# Timer-Ruler.net
KiCad netlist of a schematic drawn in EAGLE
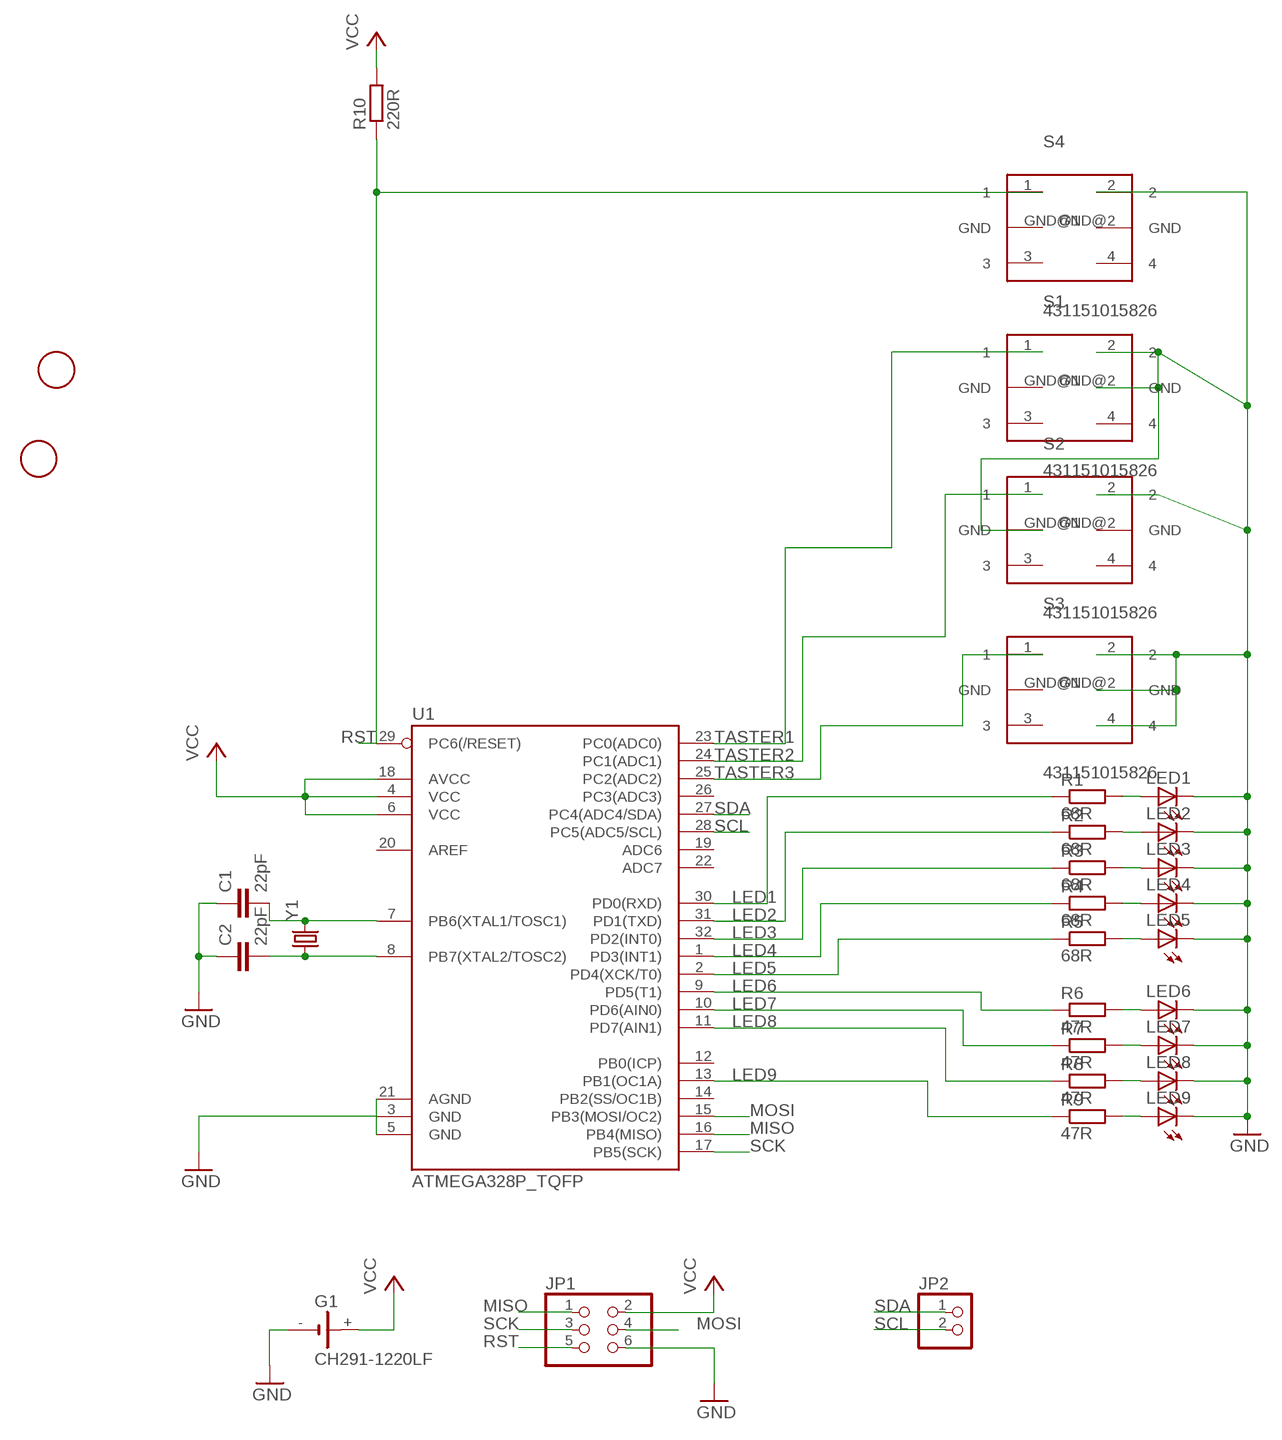
[diagram p0: schematic, sheet 1]

(export (version "E")
  (design (tool "Eeschema 10.0.6"))
  (components
    (comp (ref "C1")
      (value "22pF")
      (footprint "eagle-import:C0603")
      (libsource (lib "eagle-import") (part "C-EUC0603"))
    )
    (comp (ref "C2")
      (value "22pF")
      (footprint "eagle-import:C0603")
      (libsource (lib "eagle-import") (part "C-EUC0603"))
    )
    (comp (ref "G1")
      (value "CH291-1220LF")
      (footprint "eagle-import:CH291-1220LF")
      (libsource (lib "eagle-import") (part "CH291-1220LF"))
    )
    (comp (ref "JP1")
      (value "PINHD-2X3")
      (footprint "eagle-import:2X03")
      (libsource (lib "eagle-import") (part "PINHD-2X3"))
    )
    (comp (ref "JP2")
      (value "PINHD-1X2")
      (footprint "eagle-import:1X02")
      (libsource (lib "eagle-import") (part "PINHD-1X2"))
    )
    (comp (ref "LED1")
      (value "LEDCHIP-LED0805")
      (footprint "eagle-import:CHIP-LED0805")
      (libsource (lib "eagle-import") (part "LEDCHIP-LED0805"))
    )
    (comp (ref "LED2")
      (value "LEDCHIP-LED0805")
      (footprint "eagle-import:CHIP-LED0805")
      (libsource (lib "eagle-import") (part "LEDCHIP-LED0805"))
    )
    (comp (ref "LED3")
      (value "LEDCHIP-LED0805")
      (footprint "eagle-import:CHIP-LED0805")
      (libsource (lib "eagle-import") (part "LEDCHIP-LED0805"))
    )
    (comp (ref "LED4")
      (value "LEDCHIP-LED0805")
      (footprint "eagle-import:CHIP-LED0805")
      (libsource (lib "eagle-import") (part "LEDCHIP-LED0805"))
    )
    (comp (ref "LED5")
      (value "LEDCHIP-LED0805")
      (footprint "eagle-import:CHIP-LED0805")
      (libsource (lib "eagle-import") (part "LEDCHIP-LED0805"))
    )
    (comp (ref "LED6")
      (value "LEDCHIP-LED0805")
      (footprint "eagle-import:CHIP-LED0805")
      (libsource (lib "eagle-import") (part "LEDCHIP-LED0805"))
    )
    (comp (ref "LED7")
      (value "LEDCHIP-LED0805")
      (footprint "eagle-import:CHIP-LED0805")
      (libsource (lib "eagle-import") (part "LEDCHIP-LED0805"))
    )
    (comp (ref "LED8")
      (value "LEDCHIP-LED0805")
      (footprint "eagle-import:CHIP-LED0805")
      (libsource (lib "eagle-import") (part "LEDCHIP-LED0805"))
    )
    (comp (ref "LED9")
      (value "LEDCHIP-LED0805")
      (footprint "eagle-import:CHIP-LED0805")
      (libsource (lib "eagle-import") (part "LEDCHIP-LED0805"))
    )
    (comp (ref "R1")
      (value "68R")
      (footprint "eagle-import:R0603")
      (libsource (lib "eagle-import") (part "R-EU_R0603"))
    )
    (comp (ref "R2")
      (value "68R")
      (footprint "eagle-import:R0603")
      (libsource (lib "eagle-import") (part "R-EU_R0603"))
    )
    (comp (ref "R3")
      (value "68R")
      (footprint "eagle-import:R0603")
      (libsource (lib "eagle-import") (part "R-EU_R0603"))
    )
    (comp (ref "R4")
      (value "68R")
      (footprint "eagle-import:R0603")
      (libsource (lib "eagle-import") (part "R-EU_R0603"))
    )
    (comp (ref "R5")
      (value "68R")
      (footprint "eagle-import:R0603")
      (libsource (lib "eagle-import") (part "R-EU_R0603"))
    )
    (comp (ref "R6")
      (value "47R")
      (footprint "eagle-import:R0603")
      (libsource (lib "eagle-import") (part "R-EU_R0603"))
    )
    (comp (ref "R7")
      (value "47R")
      (footprint "eagle-import:R0603")
      (libsource (lib "eagle-import") (part "R-EU_R0603"))
    )
    (comp (ref "R8")
      (value "47R")
      (footprint "eagle-import:R0603")
      (libsource (lib "eagle-import") (part "R-EU_R0603"))
    )
    (comp (ref "R9")
      (value "47R")
      (footprint "eagle-import:R0603")
      (libsource (lib "eagle-import") (part "R-EU_R0603"))
    )
    (comp (ref "R10")
      (value "220R")
      (footprint "eagle-import:R0603")
      (libsource (lib "eagle-import") (part "R-EU_R0603"))
    )
    (comp (ref "S1")
      (value "431151015826")
      (footprint "eagle-import:431181015816")
      (libsource (lib "eagle-import") (part "431151015826"))
    )
    (comp (ref "S2")
      (value "431151015826")
      (footprint "eagle-import:431181015816")
      (libsource (lib "eagle-import") (part "431151015826"))
    )
    (comp (ref "S3")
      (value "431151015826")
      (footprint "eagle-import:431181015816")
      (libsource (lib "eagle-import") (part "431151015826"))
    )
    (comp (ref "S4")
      (value "431151015826")
      (footprint "eagle-import:431181015816")
      (libsource (lib "eagle-import") (part "431151015826"))
    )
    (comp (ref "U$1")
      (value "FIDUCIAL")
      (footprint "eagle-import:FIDUCIAL_1MM")
      (libsource (lib "eagle-import") (part "FIDUCIAL"))
    )
    (comp (ref "U$2")
      (value "FIDUCIAL")
      (footprint "eagle-import:FIDUCIAL_1MM")
      (libsource (lib "eagle-import") (part "FIDUCIAL"))
    )
    (comp (ref "U1")
      (value "ATMEGA328P_TQFP")
      (footprint "eagle-import:TQFP32-08")
      (libsource (lib "eagle-import") (part "ATMEGA328P_TQFP"))
    )
    (comp (ref "Y1")
      (value "CRYSTALCRYSTAL-SMD-5X3-12.288MHZ")
      (footprint "eagle-import:CRYSTAL-SMD-5X3")
      (libsource (lib "eagle-import") (part "CRYSTALCRYSTAL-SMD-5X3-12.288MHZ"))
    )
  )
  (nets
    (net (code "1") (name "/LED1") (class "Default")
      (node (ref "R1") (pin "1") (pinfunction "1_1") (pintype "passive"))
      (node (ref "U1") (pin "30") (pinfunction "PD0(RXD)_30") (pintype "bidirectional"))
    )
    (net (code "2") (name "/LED2") (class "Default")
      (node (ref "R2") (pin "1") (pinfunction "1_1") (pintype "passive"))
      (node (ref "U1") (pin "31") (pinfunction "PD1(TXD)_31") (pintype "bidirectional"))
    )
    (net (code "3") (name "/LED3") (class "Default")
      (node (ref "R3") (pin "1") (pinfunction "1_1") (pintype "passive"))
      (node (ref "U1") (pin "32") (pinfunction "PD2(INT0)_32") (pintype "bidirectional"))
    )
    (net (code "4") (name "/LED4") (class "Default")
      (node (ref "R4") (pin "1") (pinfunction "1_1") (pintype "passive"))
      (node (ref "U1") (pin "1") (pinfunction "PD3(INT1)_1") (pintype "bidirectional"))
    )
    (net (code "5") (name "/LED5") (class "Default")
      (node (ref "R5") (pin "1") (pinfunction "1_1") (pintype "passive"))
      (node (ref "U1") (pin "2") (pinfunction "PD4(XCK/T0)_2") (pintype "bidirectional"))
    )
    (net (code "6") (name "/LED6") (class "Default")
      (node (ref "R6") (pin "1") (pinfunction "1_1") (pintype "passive"))
      (node (ref "U1") (pin "9") (pinfunction "PD5(T1)_9") (pintype "bidirectional"))
    )
    (net (code "7") (name "/LED7") (class "Default")
      (node (ref "R7") (pin "1") (pinfunction "1_1") (pintype "passive"))
      (node (ref "U1") (pin "10") (pinfunction "PD6(AIN0)_10") (pintype "bidirectional"))
    )
    (net (code "8") (name "/LED8") (class "Default")
      (node (ref "R8") (pin "1") (pinfunction "1_1") (pintype "passive"))
      (node (ref "U1") (pin "11") (pinfunction "PD7(AIN1)_11") (pintype "bidirectional"))
    )
    (net (code "9") (name "/LED9") (class "Default")
      (node (ref "R9") (pin "1") (pinfunction "1_1") (pintype "passive"))
      (node (ref "U1") (pin "13") (pinfunction "PB1(OC1A)_13") (pintype "bidirectional"))
    )
    (net (code "10") (name "/MISO") (class "Default")
      (node (ref "JP1") (pin "1") (pinfunction "1_1") (pintype "passive"))
      (node (ref "U1") (pin "16") (pinfunction "PB4(MISO)_16") (pintype "bidirectional"))
    )
    (net (code "11") (name "/MOSI") (class "Default")
      (node (ref "JP1") (pin "4") (pinfunction "4_4") (pintype "passive"))
      (node (ref "U1") (pin "15") (pinfunction "PB3(MOSI/OC2)_15") (pintype "bidirectional"))
    )
    (net (code "12") (name "/RST") (class "Default")
      (node (ref "JP1") (pin "5") (pinfunction "5_5") (pintype "passive"))
      (node (ref "R10") (pin "1") (pinfunction "1_1") (pintype "passive"))
      (node (ref "S4") (pin "1") (pinfunction "1_1") (pintype "bidirectional"))
      (node (ref "U1") (pin "29") (pinfunction "PC6(/RESET)_29") (pintype "bidirectional"))
    )
    (net (code "13") (name "/SCK") (class "Default")
      (node (ref "JP1") (pin "3") (pinfunction "3_3") (pintype "passive"))
      (node (ref "U1") (pin "17") (pinfunction "PB5(SCK)_17") (pintype "bidirectional"))
    )
    (net (code "14") (name "/SCL") (class "Default")
      (node (ref "JP2") (pin "2") (pinfunction "2_2") (pintype "passive"))
      (node (ref "U1") (pin "28") (pinfunction "PC5(ADC5/SCL)_28") (pintype "bidirectional"))
    )
    (net (code "15") (name "/SDA") (class "Default")
      (node (ref "JP2") (pin "1") (pinfunction "1_1") (pintype "passive"))
      (node (ref "U1") (pin "27") (pinfunction "PC4(ADC4/SDA)_27") (pintype "bidirectional"))
    )
    (net (code "16") (name "/TASTER1") (class "Default")
      (node (ref "S1") (pin "1") (pinfunction "1_1") (pintype "bidirectional"))
      (node (ref "U1") (pin "23") (pinfunction "PC0(ADC0)_23") (pintype "bidirectional"))
    )
    (net (code "17") (name "/TASTER2") (class "Default")
      (node (ref "S2") (pin "1") (pinfunction "1_1") (pintype "bidirectional"))
      (node (ref "U1") (pin "24") (pinfunction "PC1(ADC1)_24") (pintype "bidirectional"))
    )
    (net (code "18") (name "/TASTER3") (class "Default")
      (node (ref "S3") (pin "1") (pinfunction "1_1") (pintype "bidirectional"))
      (node (ref "U1") (pin "25") (pinfunction "PC2(ADC2)_25") (pintype "bidirectional"))
    )
    (net (code "19") (name "GND") (class "Default")
      (node (ref "C1") (pin "1") (pinfunction "1_1") (pintype "passive"))
      (node (ref "C2") (pin "1") (pinfunction "1_1") (pintype "passive"))
      (node (ref "G1") (pin "-") (pinfunction "-_-") (pintype "passive"))
      (node (ref "JP1") (pin "6") (pinfunction "6_6") (pintype "passive"))
      (node (ref "LED1") (pin "C") (pinfunction "C_C") (pintype "passive"))
      (node (ref "LED2") (pin "C") (pinfunction "C_C") (pintype "passive"))
      (node (ref "LED3") (pin "C") (pinfunction "C_C") (pintype "passive"))
      (node (ref "LED4") (pin "C") (pinfunction "C_C") (pintype "passive"))
      (node (ref "LED5") (pin "C") (pinfunction "C_C") (pintype "passive"))
      (node (ref "LED6") (pin "C") (pinfunction "C_C") (pintype "passive"))
      (node (ref "LED7") (pin "C") (pinfunction "C_C") (pintype "passive"))
      (node (ref "LED8") (pin "C") (pinfunction "C_C") (pintype "passive"))
      (node (ref "LED9") (pin "C") (pinfunction "C_C") (pintype "passive"))
      (node (ref "S1") (pin "2") (pinfunction "2_2") (pintype "bidirectional"))
      (node (ref "S1") (pin "GND@2") (pinfunction "GND_GND@2") (pintype "bidirectional"))
      (node (ref "S2") (pin "2") (pinfunction "2_2") (pintype "bidirectional"))
      (node (ref "S2") (pin "GND@1") (pinfunction "GND_GND@1") (pintype "bidirectional"))
      (node (ref "S3") (pin "2") (pinfunction "2_2") (pintype "bidirectional"))
      (node (ref "S3") (pin "4") (pinfunction "4_4") (pintype "bidirectional"))
      (node (ref "S3") (pin "GND@2") (pinfunction "GND_GND@2") (pintype "bidirectional"))
      (node (ref "S4") (pin "2") (pinfunction "2_2") (pintype "bidirectional"))
      (node (ref "U1") (pin "3") (pinfunction "GND_3") (pintype "bidirectional"))
    )
    (net (code "20") (name "Net-(LED1-PadA)") (class "Default")
      (node (ref "LED1") (pin "A") (pinfunction "A_A") (pintype "passive"))
      (node (ref "R1") (pin "2") (pinfunction "2_2") (pintype "passive"))
    )
    (net (code "21") (name "Net-(LED2-PadA)") (class "Default")
      (node (ref "LED2") (pin "A") (pinfunction "A_A") (pintype "passive"))
      (node (ref "R2") (pin "2") (pinfunction "2_2") (pintype "passive"))
    )
    (net (code "22") (name "Net-(LED3-PadA)") (class "Default")
      (node (ref "LED3") (pin "A") (pinfunction "A_A") (pintype "passive"))
      (node (ref "R3") (pin "2") (pinfunction "2_2") (pintype "passive"))
    )
    (net (code "23") (name "Net-(LED4-PadA)") (class "Default")
      (node (ref "LED4") (pin "A") (pinfunction "A_A") (pintype "passive"))
      (node (ref "R4") (pin "2") (pinfunction "2_2") (pintype "passive"))
    )
    (net (code "24") (name "Net-(LED5-PadA)") (class "Default")
      (node (ref "LED5") (pin "A") (pinfunction "A_A") (pintype "passive"))
      (node (ref "R5") (pin "2") (pinfunction "2_2") (pintype "passive"))
    )
    (net (code "25") (name "Net-(LED6-PadA)") (class "Default")
      (node (ref "LED6") (pin "A") (pinfunction "A_A") (pintype "passive"))
      (node (ref "R6") (pin "2") (pinfunction "2_2") (pintype "passive"))
    )
    (net (code "26") (name "Net-(LED7-PadA)") (class "Default")
      (node (ref "LED7") (pin "A") (pinfunction "A_A") (pintype "passive"))
      (node (ref "R7") (pin "2") (pinfunction "2_2") (pintype "passive"))
    )
    (net (code "27") (name "Net-(LED8-PadA)") (class "Default")
      (node (ref "LED8") (pin "A") (pinfunction "A_A") (pintype "passive"))
      (node (ref "R8") (pin "2") (pinfunction "2_2") (pintype "passive"))
    )
    (net (code "28") (name "Net-(LED9-PadA)") (class "Default")
      (node (ref "LED9") (pin "A") (pinfunction "A_A") (pintype "passive"))
      (node (ref "R9") (pin "2") (pinfunction "2_2") (pintype "passive"))
    )
    (net (code "29") (name "Net-(U1-AGND)") (class "Default")
      (node (ref "U1") (pin "21") (pinfunction "AGND_21") (pintype "bidirectional"))
      (node (ref "U1") (pin "5") (pinfunction "GND_5") (pintype "bidirectional"))
    )
    (net (code "30") (name "Net-(U1-PB6(XTAL1{slash}TOSC1))") (class "Default")
      (node (ref "C1") (pin "2") (pinfunction "2_2") (pintype "passive"))
      (node (ref "U1") (pin "7") (pinfunction "PB6(XTAL1/TOSC1)_7") (pintype "bidirectional"))
      (node (ref "Y1") (pin "3") (pinfunction "2_3") (pintype "passive"))
    )
    (net (code "31") (name "Net-(U1-PB7(XTAL2{slash}TOSC2))") (class "Default")
      (node (ref "C2") (pin "2") (pinfunction "2_2") (pintype "passive"))
      (node (ref "U1") (pin "8") (pinfunction "PB7(XTAL2/TOSC2)_8") (pintype "bidirectional"))
      (node (ref "Y1") (pin "1") (pinfunction "1_1") (pintype "passive"))
    )
    (net (code "32") (name "VCC") (class "Default")
      (node (ref "G1") (pin "+") (pinfunction "+_+") (pintype "passive"))
      (node (ref "JP1") (pin "2") (pinfunction "2_2") (pintype "passive"))
      (node (ref "R10") (pin "2") (pinfunction "2_2") (pintype "passive"))
      (node (ref "U1") (pin "18") (pinfunction "AVCC_18") (pintype "bidirectional"))
      (node (ref "U1") (pin "4") (pinfunction "VCC_4") (pintype "bidirectional"))
      (node (ref "U1") (pin "6") (pinfunction "VCC_6") (pintype "bidirectional"))
    )
    (net (code "33") (name "unconnected-(S1-GND-PadGND@1)") (class "Default")
      (node (ref "S1") (pin "GND@1") (pinfunction "GND_GND@1") (pintype "bidirectional"))
    )
    (net (code "34") (name "unconnected-(S1-Pad3)") (class "Default")
      (node (ref "S1") (pin "3") (pinfunction "3_3") (pintype "bidirectional"))
    )
    (net (code "35") (name "unconnected-(S1-Pad4)") (class "Default")
      (node (ref "S1") (pin "4") (pinfunction "4_4") (pintype "bidirectional"))
    )
    (net (code "36") (name "unconnected-(S2-GND-PadGND@2)") (class "Default")
      (node (ref "S2") (pin "GND@2") (pinfunction "GND_GND@2") (pintype "bidirectional"))
    )
    (net (code "37") (name "unconnected-(S2-Pad3)") (class "Default")
      (node (ref "S2") (pin "3") (pinfunction "3_3") (pintype "bidirectional"))
    )
    (net (code "38") (name "unconnected-(S2-Pad4)") (class "Default")
      (node (ref "S2") (pin "4") (pinfunction "4_4") (pintype "bidirectional"))
    )
    (net (code "39") (name "unconnected-(S3-GND-PadGND@1)") (class "Default")
      (node (ref "S3") (pin "GND@1") (pinfunction "GND_GND@1") (pintype "bidirectional"))
    )
    (net (code "40") (name "unconnected-(S3-Pad3)") (class "Default")
      (node (ref "S3") (pin "3") (pinfunction "3_3") (pintype "bidirectional"))
    )
    (net (code "41") (name "unconnected-(S4-GND-PadGND@1)") (class "Default")
      (node (ref "S4") (pin "GND@1") (pinfunction "GND_GND@1") (pintype "bidirectional"))
    )
    (net (code "42") (name "unconnected-(S4-GND-PadGND@2)") (class "Default")
      (node (ref "S4") (pin "GND@2") (pinfunction "GND_GND@2") (pintype "bidirectional"))
    )
    (net (code "43") (name "unconnected-(S4-Pad3)") (class "Default")
      (node (ref "S4") (pin "3") (pinfunction "3_3") (pintype "bidirectional"))
    )
    (net (code "44") (name "unconnected-(S4-Pad4)") (class "Default")
      (node (ref "S4") (pin "4") (pinfunction "4_4") (pintype "bidirectional"))
    )
    (net (code "45") (name "unconnected-(U1-ADC6-Pad19)") (class "Default")
      (node (ref "U1") (pin "19") (pinfunction "ADC6_19") (pintype "bidirectional"))
    )
    (net (code "46") (name "unconnected-(U1-ADC7-Pad22)") (class "Default")
      (node (ref "U1") (pin "22") (pinfunction "ADC7_22") (pintype "bidirectional"))
    )
    (net (code "47") (name "unconnected-(U1-AREF-Pad20)") (class "Default")
      (node (ref "U1") (pin "20") (pinfunction "AREF_20") (pintype "bidirectional"))
    )
    (net (code "48") (name "unconnected-(U1-PB0(ICP)-Pad12)") (class "Default")
      (node (ref "U1") (pin "12") (pinfunction "PB0(ICP)_12") (pintype "bidirectional"))
    )
    (net (code "49") (name "unconnected-(U1-PB2(SS{slash}OC1B)-Pad14)") (class "Default")
      (node (ref "U1") (pin "14") (pinfunction "PB2(SS/OC1B)_14") (pintype "bidirectional"))
    )
    (net (code "50") (name "unconnected-(U1-PC3(ADC3)-Pad26)") (class "Default")
      (node (ref "U1") (pin "26") (pinfunction "PC3(ADC3)_26") (pintype "bidirectional"))
    )
  )
)
